# AD7793.net
KiCad netlist of a schematic drawn in Altium Designer
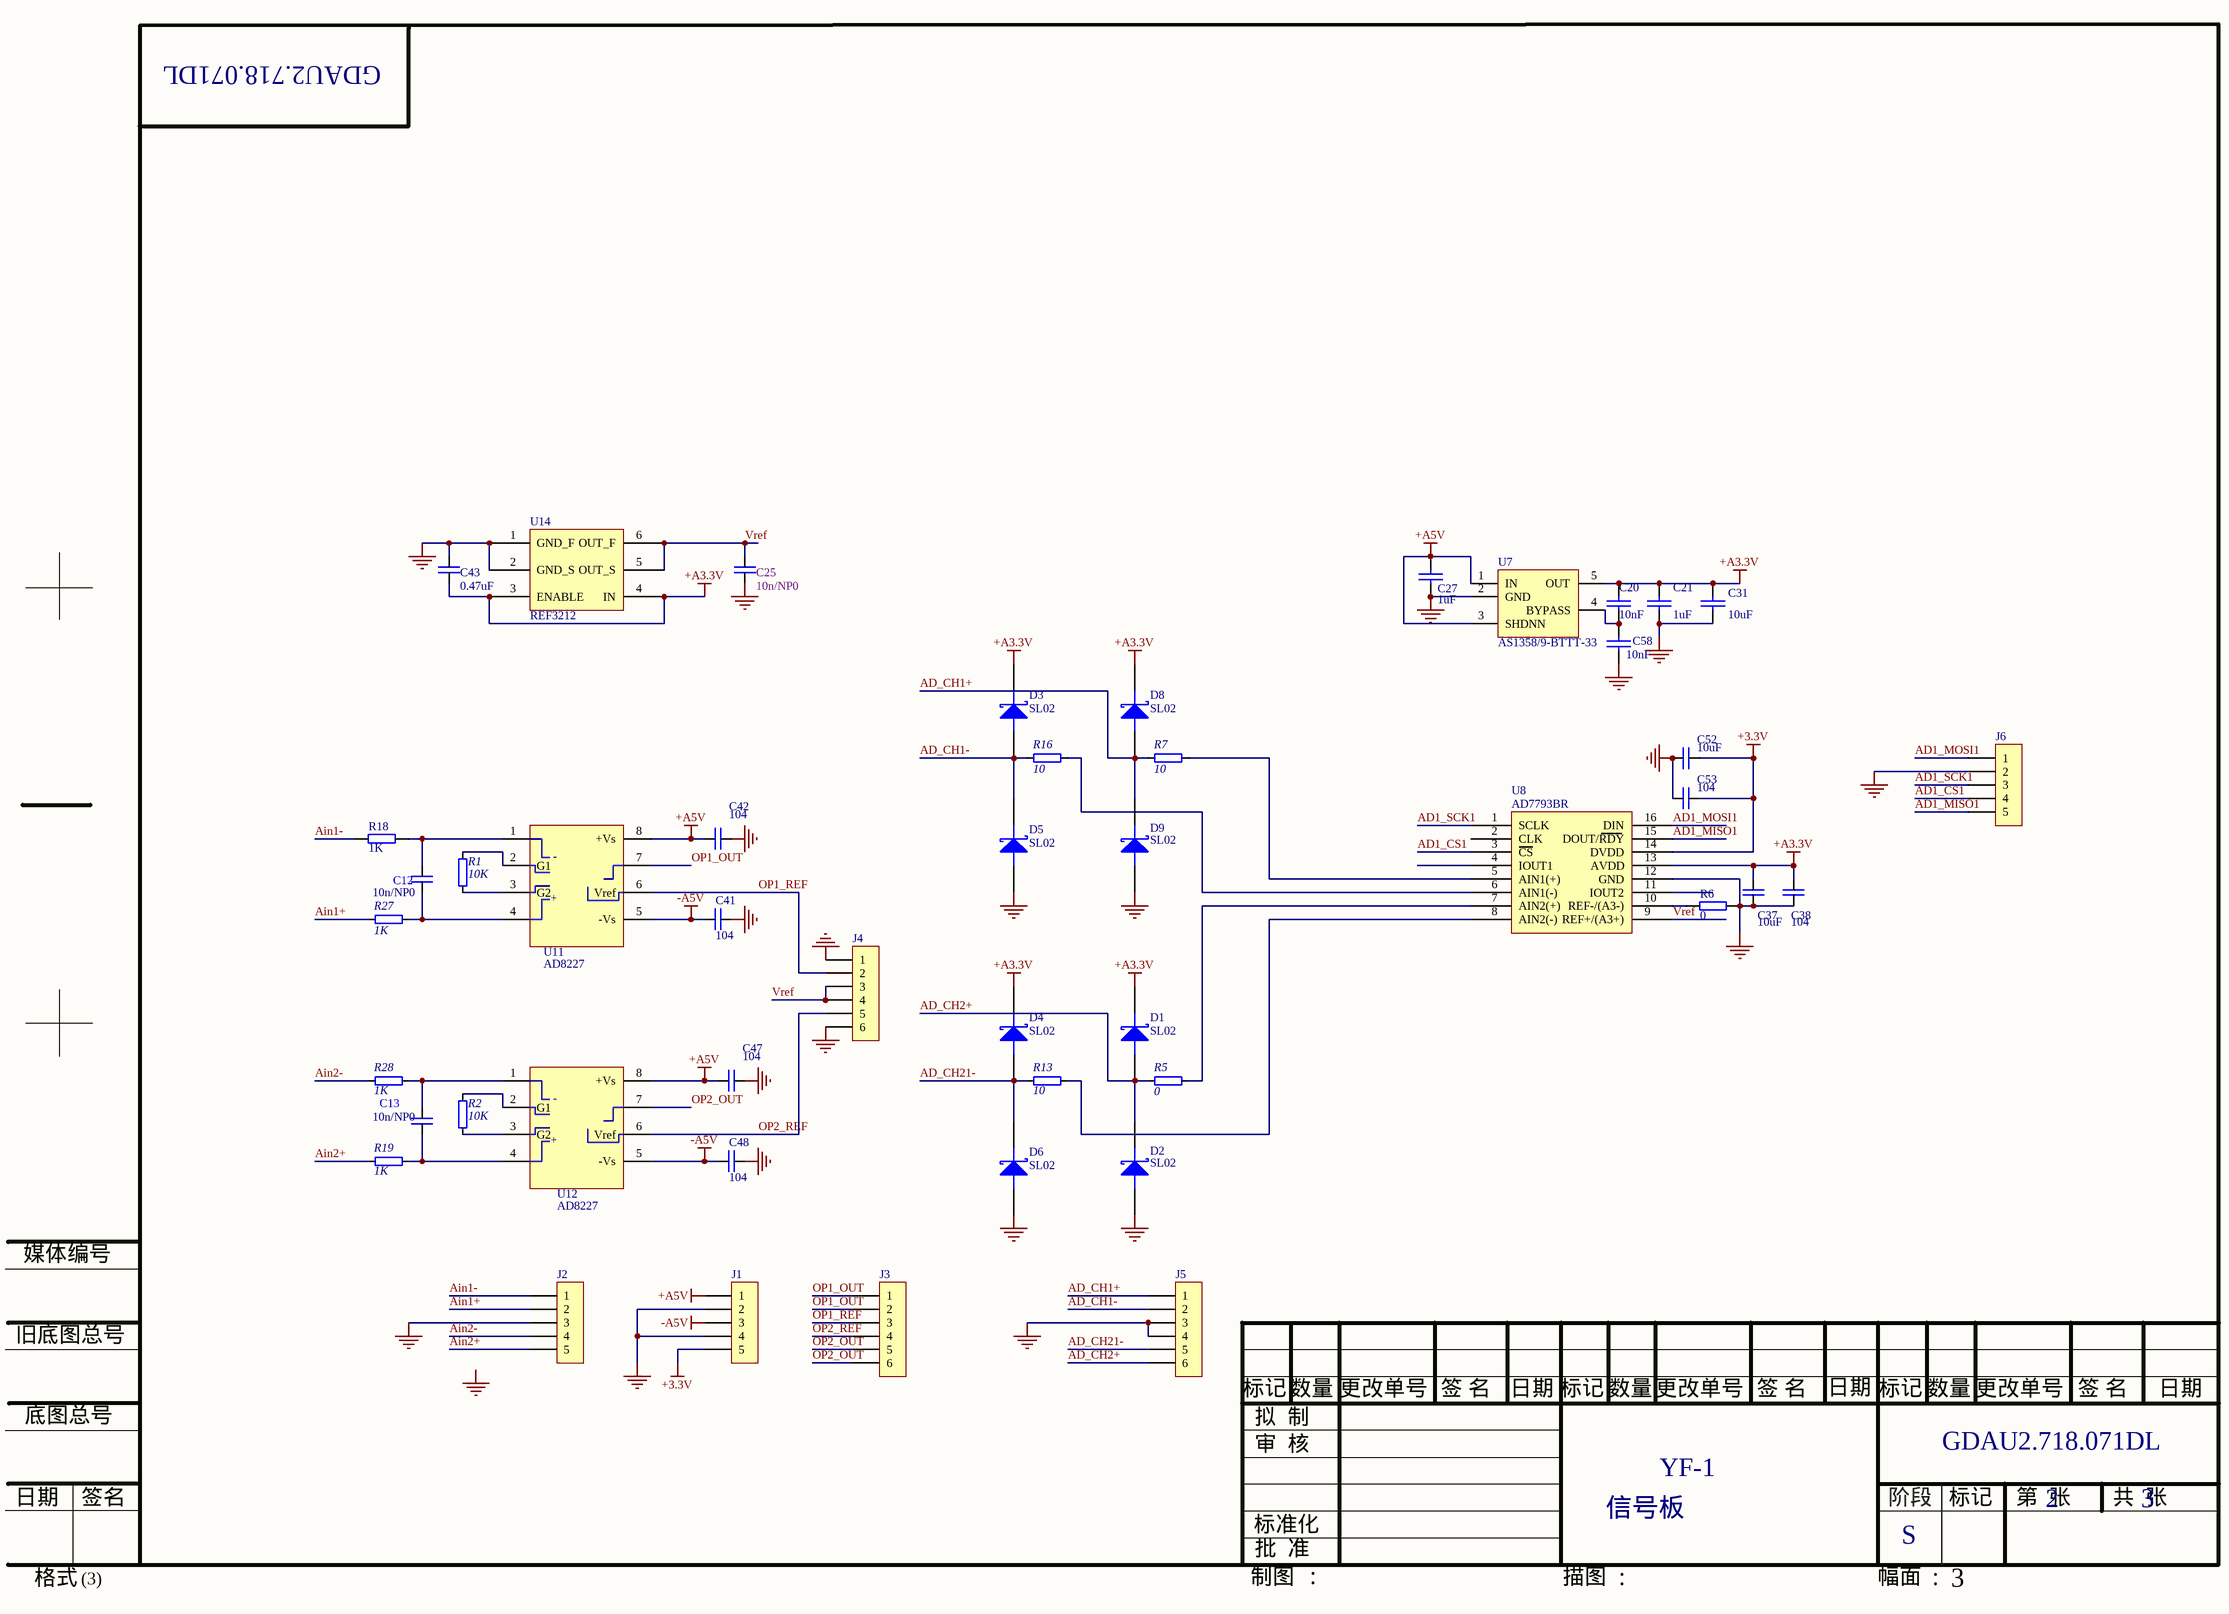
[diagram p0: AD7793.schdoc]

(export (version "E")
  (design (tool "Eeschema 10.0.6"))
  (components
    (comp (ref "C12") (value "10n/NP0") (footprint "0805") (libsource (lib "*") (part "贴片电容")))
    (comp (ref "C13") (value "10n/NP0") (footprint "0805") (libsource (lib "*") (part "贴片电容")))
    (comp (ref "C20")
      (value "10nF")
      (footprint "0603")
      (description "Capacitor")
      (libsource (lib "*") (part "CAP"))
    )
    (comp (ref "C21")
      (value "1uF")
      (footprint "0603")
      (description "Capacitor")
      (libsource (lib "*") (part "CAP"))
    )
    (comp (ref "C25") (value "10n/NP0") (footprint "0805") (libsource (lib "*") (part "贴片电容")))
    (comp (ref "C27")
      (value "1uF")
      (footprint "0603")
      (description "Capacitor")
      (libsource (lib "*") (part "CAP"))
    )
    (comp (ref "C31")
      (value "10uF")
      (footprint "0805")
      (description "Capacitor")
      (libsource (lib "*") (part "CAP"))
    )
    (comp (ref "C37") (value "10uF") (footprint "0805") (libsource (lib "*") (part "贴片电容")))
    (comp (ref "C38") (value "104") (footprint "0603") (libsource (lib "*") (part "贴片电容")))
    (comp (ref "C41") (value "104") (footprint "0603") (libsource (lib "*") (part "贴片电容")))
    (comp (ref "C42") (value "104") (footprint "0603") (libsource (lib "*") (part "贴片电容")))
    (comp (ref "C43") (value "0.47uF") (footprint "0603") (libsource (lib "*") (part "贴片电容")))
    (comp (ref "C47") (value "104") (footprint "0603") (libsource (lib "*") (part "贴片电容")))
    (comp (ref "C48") (value "104") (footprint "0603") (libsource (lib "*") (part "贴片电容")))
    (comp (ref "C52") (value "10uF") (footprint "0805") (libsource (lib "*") (part "贴片电容")))
    (comp (ref "C53") (value "104") (footprint "0603") (libsource (lib "*") (part "贴片电容")))
    (comp (ref "C58")
      (value "10nF")
      (footprint "0603")
      (description "Capacitor")
      (libsource (lib "") (part "CAP_1"))
    )
    (comp (ref "D1")
      (value "SL02")
      (footprint "DO-219AB")
      (description "Schottky Diode")
      (libsource (lib "*") (part "DIODE SCHOTTKY"))
    )
    (comp (ref "D2")
      (value "SL02")
      (footprint "DO-219AB")
      (description "Schottky Diode")
      (libsource (lib "*") (part "DIODE SCHOTTKY"))
    )
    (comp (ref "D3")
      (value "SL02")
      (footprint "DO-219AB")
      (description "Schottky Diode")
      (libsource (lib "*") (part "DIODE SCHOTTKY"))
    )
    (comp (ref "D4")
      (value "SL02")
      (footprint "DO-219AB")
      (description "Schottky Diode")
      (libsource (lib "*") (part "DIODE SCHOTTKY"))
    )
    (comp (ref "D5")
      (value "SL02")
      (footprint "DO-219AB")
      (description "Schottky Diode")
      (libsource (lib "*") (part "DIODE SCHOTTKY"))
    )
    (comp (ref "D6")
      (value "SL02")
      (footprint "DO-219AB")
      (description "Schottky Diode")
      (libsource (lib "*") (part "DIODE SCHOTTKY"))
    )
    (comp (ref "D8")
      (value "SL02")
      (footprint "DO-219AB")
      (description "Schottky Diode")
      (libsource (lib "*") (part "DIODE SCHOTTKY"))
    )
    (comp (ref "D9")
      (value "SL02")
      (footprint "DO-219AB")
      (description "Schottky Diode")
      (libsource (lib "*") (part "DIODE SCHOTTKY"))
    )
    (comp (ref "J1")
      (value "~")
      (footprint "SIP5")
      (description "Connector")
      (libsource (lib "*") (part "CON5"))
    )
    (comp (ref "J2")
      (value "~")
      (footprint "SIP5")
      (description "Connector")
      (libsource (lib "*") (part "CON5"))
    )
    (comp (ref "J3")
      (value "~")
      (footprint "SIP6")
      (description "Connector")
      (libsource (lib "*") (part "CON6"))
    )
    (comp (ref "J4")
      (value "~")
      (footprint "SIP6")
      (description "Connector")
      (libsource (lib "*") (part "CON6"))
    )
    (comp (ref "J5")
      (value "~")
      (footprint "SIP6")
      (description "Connector")
      (libsource (lib "*") (part "CON6"))
    )
    (comp (ref "J6")
      (value "~")
      (footprint "SIP5")
      (description "Connector")
      (libsource (lib "*") (part "CON5"))
    )
    (comp (ref "R1") (value "10K") (footprint "0603") (libsource (lib "*") (part "RES2")))
    (comp (ref "R2") (value "10K") (footprint "0603") (libsource (lib "*") (part "RES2")))
    (comp (ref "R5") (value "0") (footprint "0603") (libsource (lib "*") (part "RES2")))
    (comp (ref "R6") (value "0") (footprint "0603") (libsource (lib "*") (part "贴片电阻(回流焊)")))
    (comp (ref "R7") (value "10") (footprint "0603") (libsource (lib "*") (part "RES2")))
    (comp (ref "R13") (value "10") (footprint "0603") (libsource (lib "*") (part "RES2")))
    (comp (ref "R16") (value "10") (footprint "0603") (libsource (lib "*") (part "RES2")))
    (comp (ref "R18") (value "1K") (footprint "0603") (libsource (lib "*") (part "贴片电阻(回流焊)")))
    (comp (ref "R19") (value "1K") (footprint "0603") (libsource (lib "*") (part "RES2")))
    (comp (ref "R27") (value "1K") (footprint "0603") (libsource (lib "*") (part "RES2")))
    (comp (ref "R28") (value "1K") (footprint "0603") (libsource (lib "*") (part "RES2")))
    (comp (ref "U7")
      (value "AS1358/9-BTTT-33")
      (footprint "SOT23-5")
      (description "AS1358/9")
      (libsource (lib "*") (part "稳压器AS1358/9"))
    )
    (comp (ref "U8") (value "AD7793BR") (footprint "TSSOP-16") (libsource (lib "*") (part "AD7793")))
    (comp (ref "U11")
      (value "AD8227")
      (footprint "S8")
      (description "INA282")
      (libsource (lib "*") (part "AD8228"))
    )
    (comp (ref "U12")
      (value "AD8227")
      (footprint "S8")
      (description "INA282")
      (libsource (lib "*") (part "AD8228"))
    )
    (comp (ref "U14") (value "REF3212") (footprint "SOT-23(6)") (libsource (lib "*") (part "REF3212")))
  )
  (nets
    (net (code "1") (name "+3.3V") (class "Default")
      (node (ref "C52") (pin "2") (pinfunction "2_2") (pintype "passive"))
      (node (ref "C53") (pin "2") (pinfunction "2_2") (pintype "passive"))
      (node (ref "J1") (pin "5") (pinfunction "5_5") (pintype "passive"))
      (node (ref "U8") (pin "14") (pinfunction "DVDD_14") (pintype "passive"))
    )
    (net (code "2") (name "+A3.3V") (class "Default")
      (node (ref "C20") (pin "2") (pinfunction "2_2") (pintype "passive"))
      (node (ref "C21") (pin "2") (pinfunction "2_2") (pintype "passive"))
      (node (ref "C31") (pin "1") (pinfunction "1_1") (pintype "passive"))
      (node (ref "C37") (pin "2") (pinfunction "2_2") (pintype "passive"))
      (node (ref "C38") (pin "2") (pinfunction "2_2") (pintype "passive"))
      (node (ref "C43") (pin "1") (pinfunction "1_1") (pintype "passive"))
      (node (ref "D1") (pin "K") (pinfunction "K_K") (pintype "passive"))
      (node (ref "D3") (pin "K") (pinfunction "K_K") (pintype "passive"))
      (node (ref "D4") (pin "K") (pinfunction "K_K") (pintype "passive"))
      (node (ref "D8") (pin "K") (pinfunction "K_K") (pintype "passive"))
      (node (ref "U14") (pin "3") (pinfunction "ENABLE_3") (pintype "passive"))
      (node (ref "U14") (pin "4") (pinfunction "IN_4") (pintype "passive"))
      (node (ref "U7") (pin "5") (pinfunction "OUT_5") (pintype "passive"))
      (node (ref "U8") (pin "13") (pinfunction "AVDD_13") (pintype "passive"))
    )
    (net (code "3") (name "+A5V") (class "Default")
      (node (ref "C27") (pin "1") (pinfunction "1_1") (pintype "passive"))
      (node (ref "C42") (pin "1") (pinfunction "1_1") (pintype "passive"))
      (node (ref "C47") (pin "1") (pinfunction "1_1") (pintype "passive"))
      (node (ref "J1") (pin "1") (pinfunction "1_1") (pintype "passive"))
      (node (ref "U11") (pin "8") (pinfunction "+Vs_8") (pintype "passive"))
      (node (ref "U12") (pin "8") (pinfunction "+Vs_8") (pintype "passive"))
      (node (ref "U7") (pin "1") (pinfunction "IN_1") (pintype "passive"))
      (node (ref "U7") (pin "3") (pinfunction "SHDNN_3") (pintype "passive"))
    )
    (net (code "4") (name "-A5V") (class "Default")
      (node (ref "C41") (pin "2") (pinfunction "2_2") (pintype "passive"))
      (node (ref "C48") (pin "2") (pinfunction "2_2") (pintype "passive"))
      (node (ref "J1") (pin "3") (pinfunction "3_3") (pintype "passive"))
      (node (ref "U11") (pin "5") (pinfunction "-Vs_5") (pintype "passive"))
      (node (ref "U12") (pin "5") (pinfunction "-Vs_5") (pintype "passive"))
    )
    (net (code "5") (name "/AD1_CS1") (class "Default")
      (node (ref "J6") (pin "4") (pinfunction "4_4") (pintype "passive"))
      (node (ref "U8") (pin "3") (pinfunction "CS_3") (pintype "passive"))
    )
    (net (code "6") (name "/AD1_MISO1") (class "Default")
      (node (ref "J6") (pin "5") (pinfunction "5_5") (pintype "passive"))
      (node (ref "U8") (pin "15") (pinfunction "DOUT/RDY_15") (pintype "passive"))
    )
    (net (code "7") (name "/AD1_MOSI1") (class "Default")
      (node (ref "J6") (pin "1") (pinfunction "1_1") (pintype "passive"))
      (node (ref "U8") (pin "16") (pinfunction "DIN_16") (pintype "passive"))
    )
    (net (code "8") (name "/AD1_SCK1") (class "Default")
      (node (ref "J6") (pin "3") (pinfunction "3_3") (pintype "passive"))
      (node (ref "U8") (pin "1") (pinfunction "SCLK_1") (pintype "passive"))
    )
    (net (code "9") (name "/AD_CH1+") (class "Default")
      (node (ref "D8") (pin "A") (pinfunction "A_A") (pintype "passive"))
      (node (ref "D9") (pin "K") (pinfunction "K_K") (pintype "passive"))
      (node (ref "J5") (pin "1") (pinfunction "1_1") (pintype "passive"))
      (node (ref "R7") (pin "1") (pinfunction "1_1") (pintype "passive"))
    )
    (net (code "10") (name "/AD_CH1-") (class "Default")
      (node (ref "D3") (pin "A") (pinfunction "A_A") (pintype "passive"))
      (node (ref "D5") (pin "K") (pinfunction "K_K") (pintype "passive"))
      (node (ref "J5") (pin "2") (pinfunction "2_2") (pintype "passive"))
      (node (ref "R16") (pin "1") (pinfunction "1_1") (pintype "passive"))
    )
    (net (code "11") (name "/AD_CH2+") (class "Default")
      (node (ref "D1") (pin "A") (pinfunction "A_A") (pintype "passive"))
      (node (ref "D2") (pin "K") (pinfunction "K_K") (pintype "passive"))
      (node (ref "J5") (pin "6") (pinfunction "6_6") (pintype "passive"))
      (node (ref "R5") (pin "2") (pinfunction "2_2") (pintype "passive"))
    )
    (net (code "12") (name "/AD_CH21-") (class "Default")
      (node (ref "D4") (pin "A") (pinfunction "A_A") (pintype "passive"))
      (node (ref "D6") (pin "K") (pinfunction "K_K") (pintype "passive"))
      (node (ref "J5") (pin "5") (pinfunction "5_5") (pintype "passive"))
      (node (ref "R13") (pin "2") (pinfunction "2_2") (pintype "passive"))
    )
    (net (code "13") (name "/Ain1+") (class "Default")
      (node (ref "J2") (pin "2") (pinfunction "2_2") (pintype "passive"))
      (node (ref "R27") (pin "1") (pinfunction "1_1") (pintype "passive"))
    )
    (net (code "14") (name "/Ain1-") (class "Default")
      (node (ref "J2") (pin "1") (pinfunction "1_1") (pintype "passive"))
      (node (ref "R18") (pin "1") (pinfunction "1_1") (pintype "passive"))
    )
    (net (code "15") (name "/Ain2+") (class "Default")
      (node (ref "J2") (pin "5") (pinfunction "5_5") (pintype "passive"))
      (node (ref "R19") (pin "1") (pinfunction "1_1") (pintype "passive"))
    )
    (net (code "16") (name "/Ain2-") (class "Default")
      (node (ref "J2") (pin "4") (pinfunction "4_4") (pintype "passive"))
      (node (ref "R28") (pin "1") (pinfunction "1_1") (pintype "passive"))
    )
    (net (code "17") (name "/OP1_OUT") (class "Default")
      (node (ref "J3") (pin "1") (pinfunction "1_1") (pintype "passive"))
      (node (ref "J3") (pin "2") (pinfunction "2_2") (pintype "passive"))
      (node (ref "U11") (pin "7") (pintype "passive"))
    )
    (net (code "18") (name "/OP1_REF") (class "Default")
      (node (ref "J3") (pin "3") (pinfunction "3_3") (pintype "passive"))
      (node (ref "J4") (pin "2") (pinfunction "2_2") (pintype "passive"))
      (node (ref "U11") (pin "6") (pinfunction "Vref_6") (pintype "passive"))
    )
    (net (code "19") (name "/OP2_OUT") (class "Default")
      (node (ref "J3") (pin "5") (pinfunction "5_5") (pintype "passive"))
      (node (ref "J3") (pin "6") (pinfunction "6_6") (pintype "passive"))
      (node (ref "U12") (pin "7") (pintype "passive"))
    )
    (net (code "20") (name "/OP2_REF") (class "Default")
      (node (ref "J3") (pin "4") (pinfunction "4_4") (pintype "passive"))
      (node (ref "J4") (pin "5") (pinfunction "5_5") (pintype "passive"))
      (node (ref "U12") (pin "6") (pinfunction "Vref_6") (pintype "passive"))
    )
    (net (code "21") (name "/Vref") (class "Default")
      (node (ref "C25") (pin "2") (pinfunction "2_2") (pintype "passive"))
      (node (ref "J4") (pin "3") (pinfunction "3_3") (pintype "passive"))
      (node (ref "J4") (pin "4") (pinfunction "4_4") (pintype "passive"))
      (node (ref "U14") (pin "5") (pinfunction "OUT_S_5") (pintype "passive"))
      (node (ref "U14") (pin "6") (pinfunction "OUT_F_6") (pintype "passive"))
      (node (ref "U8") (pin "9") (pinfunction "REF+/(A3+)_9") (pintype "passive"))
    )
    (net (code "22") (name "GND") (class "Default")
      (node (ref "C21") (pin "1") (pinfunction "1_1") (pintype "passive"))
      (node (ref "C25") (pin "1") (pinfunction "1_1") (pintype "passive"))
      (node (ref "C27") (pin "2") (pinfunction "2_2") (pintype "passive"))
      (node (ref "C31") (pin "2") (pinfunction "2_2") (pintype "passive"))
      (node (ref "C37") (pin "1") (pinfunction "1_1") (pintype "passive"))
      (node (ref "C38") (pin "1") (pinfunction "1_1") (pintype "passive"))
      (node (ref "C41") (pin "1") (pinfunction "1_1") (pintype "passive"))
      (node (ref "C42") (pin "2") (pinfunction "2_2") (pintype "passive"))
      (node (ref "C43") (pin "2") (pinfunction "2_2") (pintype "passive"))
      (node (ref "C47") (pin "2") (pinfunction "2_2") (pintype "passive"))
      (node (ref "C48") (pin "1") (pinfunction "1_1") (pintype "passive"))
      (node (ref "C52") (pin "1") (pinfunction "1_1") (pintype "passive"))
      (node (ref "C53") (pin "1") (pinfunction "1_1") (pintype "passive"))
      (node (ref "C58") (pin "1") (pinfunction "1_1") (pintype "passive"))
      (node (ref "D2") (pin "A") (pinfunction "A_A") (pintype "passive"))
      (node (ref "D5") (pin "A") (pinfunction "A_A") (pintype "passive"))
      (node (ref "D6") (pin "A") (pinfunction "A_A") (pintype "passive"))
      (node (ref "D9") (pin "A") (pinfunction "A_A") (pintype "passive"))
      (node (ref "J1") (pin "2") (pinfunction "2_2") (pintype "passive"))
      (node (ref "J1") (pin "4") (pinfunction "4_4") (pintype "passive"))
      (node (ref "J2") (pin "3") (pinfunction "3_3") (pintype "passive"))
      (node (ref "J4") (pin "1") (pinfunction "1_1") (pintype "passive"))
      (node (ref "J4") (pin "6") (pinfunction "6_6") (pintype "passive"))
      (node (ref "J5") (pin "3") (pinfunction "3_3") (pintype "passive"))
      (node (ref "J5") (pin "4") (pinfunction "4_4") (pintype "passive"))
      (node (ref "J6") (pin "2") (pinfunction "2_2") (pintype "passive"))
      (node (ref "R6") (pin "1") (pinfunction "1_1") (pintype "passive"))
      (node (ref "U14") (pin "1") (pinfunction "GND_F_1") (pintype "passive"))
      (node (ref "U14") (pin "2") (pinfunction "GND_S_2") (pintype "passive"))
      (node (ref "U7") (pin "2") (pinfunction "GND_2") (pintype "passive"))
      (node (ref "U8") (pin "12") (pinfunction "GND_12") (pintype "passive"))
    )
    (net (code "23") (name "Net-(C12-Pad1)") (class "Default")
      (node (ref "C12") (pin "1") (pinfunction "1_1") (pintype "passive"))
      (node (ref "R27") (pin "2") (pinfunction "2_2") (pintype "passive"))
      (node (ref "U11") (pin "4") (pintype "passive"))
    )
    (net (code "24") (name "Net-(C12-Pad2)") (class "Default")
      (node (ref "C12") (pin "2") (pinfunction "2_2") (pintype "passive"))
      (node (ref "R18") (pin "2") (pinfunction "2_2") (pintype "passive"))
      (node (ref "U11") (pin "1") (pintype "passive"))
    )
    (net (code "25") (name "Net-(C13-Pad1)") (class "Default")
      (node (ref "C13") (pin "1") (pinfunction "1_1") (pintype "passive"))
      (node (ref "R28") (pin "2") (pinfunction "2_2") (pintype "passive"))
      (node (ref "U12") (pin "1") (pintype "passive"))
    )
    (net (code "26") (name "Net-(C13-Pad2)") (class "Default")
      (node (ref "C13") (pin "2") (pinfunction "2_2") (pintype "passive"))
      (node (ref "R19") (pin "2") (pinfunction "2_2") (pintype "passive"))
      (node (ref "U12") (pin "4") (pintype "passive"))
    )
    (net (code "27") (name "Net-(U7-BYPASS)") (class "Default")
      (node (ref "C20") (pin "1") (pinfunction "1_1") (pintype "passive"))
      (node (ref "C58") (pin "2") (pinfunction "2_2") (pintype "passive"))
      (node (ref "U7") (pin "4") (pinfunction "BYPASS_4") (pintype "passive"))
    )
    (net (code "28") (name "Net-(U8-AIN1(+))") (class "Default")
      (node (ref "R7") (pin "2") (pinfunction "2_2") (pintype "passive"))
      (node (ref "U8") (pin "5") (pinfunction "AIN1(+)_5") (pintype "passive"))
    )
    (net (code "29") (name "Net-(U8-AIN1(-))") (class "Default")
      (node (ref "R16") (pin "2") (pinfunction "2_2") (pintype "passive"))
      (node (ref "U8") (pin "6") (pinfunction "AIN1(-)_6") (pintype "passive"))
    )
    (net (code "30") (name "Net-(U8-AIN2(+))") (class "Default")
      (node (ref "R5") (pin "1") (pinfunction "1_1") (pintype "passive"))
      (node (ref "U8") (pin "7") (pinfunction "AIN2(+)_7") (pintype "passive"))
    )
    (net (code "31") (name "Net-(U8-AIN2(-))") (class "Default")
      (node (ref "R13") (pin "1") (pinfunction "1_1") (pintype "passive"))
      (node (ref "U8") (pin "8") (pinfunction "AIN2(-)_8") (pintype "passive"))
    )
    (net (code "32") (name "Net-(U8-REF-{slash}(A3-))") (class "Default")
      (node (ref "R6") (pin "2") (pinfunction "2_2") (pintype "passive"))
      (node (ref "U8") (pin "10") (pinfunction "REF-/(A3-)_10") (pintype "passive"))
    )
    (net (code "33") (name "Net-(U11-G1)") (class "Default")
      (node (ref "R1") (pin "1") (pinfunction "1_1") (pintype "passive"))
      (node (ref "U11") (pin "2") (pinfunction "G1_2") (pintype "passive"))
    )
    (net (code "34") (name "Net-(U11-G2)") (class "Default")
      (node (ref "R1") (pin "2") (pinfunction "2_2") (pintype "passive"))
      (node (ref "U11") (pin "3") (pinfunction "G2_3") (pintype "passive"))
    )
    (net (code "35") (name "Net-(U12-G1)") (class "Default")
      (node (ref "R2") (pin "1") (pinfunction "1_1") (pintype "passive"))
      (node (ref "U12") (pin "2") (pinfunction "G1_2") (pintype "passive"))
    )
    (net (code "36") (name "Net-(U12-G2)") (class "Default")
      (node (ref "R2") (pin "2") (pinfunction "2_2") (pintype "passive"))
      (node (ref "U12") (pin "3") (pinfunction "G2_3") (pintype "passive"))
    )
    (net (code "37") (name "unconnected-(U8-CLK-Pad2)") (class "Default")
      (node (ref "U8") (pin "2") (pinfunction "CLK_2") (pintype "passive"))
    )
    (net (code "38") (name "unconnected-(U8-IOUT1-Pad4)") (class "Default")
      (node (ref "U8") (pin "4") (pinfunction "IOUT1_4") (pintype "passive"))
    )
    (net (code "39") (name "unconnected-(U8-IOUT2-Pad11)") (class "Default")
      (node (ref "U8") (pin "11") (pinfunction "IOUT2_11") (pintype "passive"))
    )
  )
)
